# Button3x4S-2_Sch.net
KiCad netlist of a schematic drawn in Altium Designer
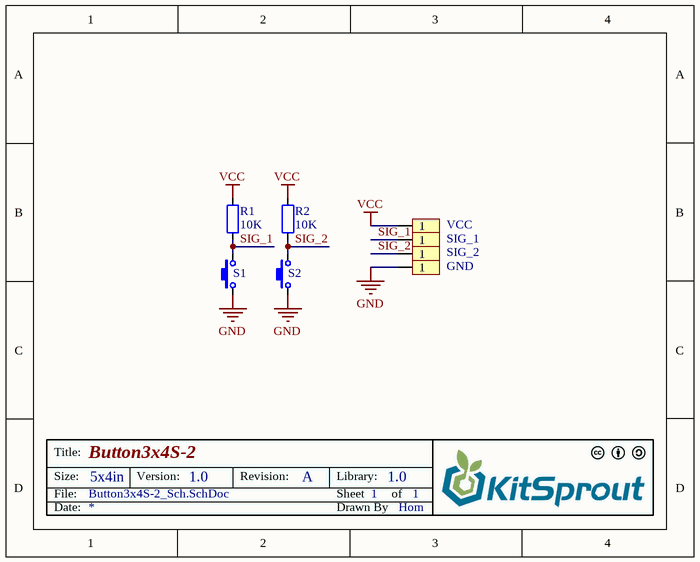
[diagram p0: Button3x4S-2_Sch.SchDoc]

(export (version "E")
  (design (tool "Eeschema 10.0.6"))
  (components
    (comp (ref "GND")
      (value "HDR-PAD_2.54")
      (footprint "PCB_ConnectorHDR:HDR-PAD_2.54")
      (description "Header")
      (libsource (lib "SCH_ConnectorHDR") (part "HDR-PAD_2.54"))
    )
    (comp (ref "R1")
      (value "10K")
      (footprint "PCB_PassiveRes:RES_0603")
      (description "Resistor")
      (fields (field (name "Comment") "Res_0603"))
      (libsource (lib "SCH_Passive") (part "Res_0603"))
    )
    (comp (ref "R2")
      (value "10K")
      (footprint "PCB_PassiveRes:RES_0603")
      (description "Resistor")
      (fields (field (name "Comment") "Res_0603"))
      (libsource (lib "SCH_Passive") (part "Res_0603"))
    )
    (comp (ref "S1")
      (value "ButtonTACT_3x4x2_180")
      (footprint "PCB_Switch:ButtonTACT_3x4x2_180H")
      (description "Button")
      (libsource (lib "SCH_Switch") (part "ButtonTACT_3x4x2_180"))
    )
    (comp (ref "S2")
      (value "ButtonTACT_3x4x2_180")
      (footprint "PCB_Switch:ButtonTACT_3x4x2_180H")
      (description "Button")
      (libsource (lib "SCH_Switch") (part "ButtonTACT_3x4x2_180"))
    )
    (comp (ref "SIG_1")
      (value "HDR-PAD_2.54")
      (footprint "PCB_ConnectorHDR:HDR-PAD_2.54")
      (description "Header")
      (libsource (lib "SCH_ConnectorHDR") (part "HDR-PAD_2.54"))
    )
    (comp (ref "SIG_2")
      (value "HDR-PAD_2.54")
      (footprint "PCB_ConnectorHDR:HDR-PAD_2.54")
      (description "Header")
      (libsource (lib "SCH_ConnectorHDR") (part "HDR-PAD_2.54"))
    )
    (comp (ref "VCC")
      (value "HDR-PAD_2.54")
      (footprint "PCB_ConnectorHDR:HDR-PAD_2.54")
      (description "Header")
      (libsource (lib "SCH_ConnectorHDR") (part "HDR-PAD_2.54"))
    )
  )
  (nets
    (net (code "1") (name "/SIG_1") (class "Default")
      (node (ref "R1") (pin "1") (pinfunction "1_1") (pintype "passive"))
      (node (ref "S1") (pin "2") (pinfunction "2_2") (pintype "passive"))
      (node (ref "SIG_1") (pin "1") (pinfunction "1_1") (pintype "passive"))
    )
    (net (code "2") (name "/SIG_2") (class "Default")
      (node (ref "R2") (pin "1") (pinfunction "1_1") (pintype "passive"))
      (node (ref "S2") (pin "2") (pinfunction "2_2") (pintype "passive"))
      (node (ref "SIG_2") (pin "1") (pinfunction "1_1") (pintype "passive"))
    )
    (net (code "3") (name "GND") (class "Default")
      (node (ref "GND") (pin "1") (pinfunction "1_1") (pintype "passive"))
      (node (ref "S1") (pin "1") (pinfunction "1_1") (pintype "passive"))
      (node (ref "S2") (pin "1") (pinfunction "1_1") (pintype "passive"))
    )
    (net (code "4") (name "VCC") (class "Default")
      (node (ref "R1") (pin "2") (pinfunction "2_2") (pintype "passive"))
      (node (ref "R2") (pin "2") (pinfunction "2_2") (pintype "passive"))
      (node (ref "VCC") (pin "1") (pinfunction "1_1") (pintype "passive"))
    )
  )
)
